# Wroom_board3motor.net
KiCad netlist of a schematic drawn in EAGLE
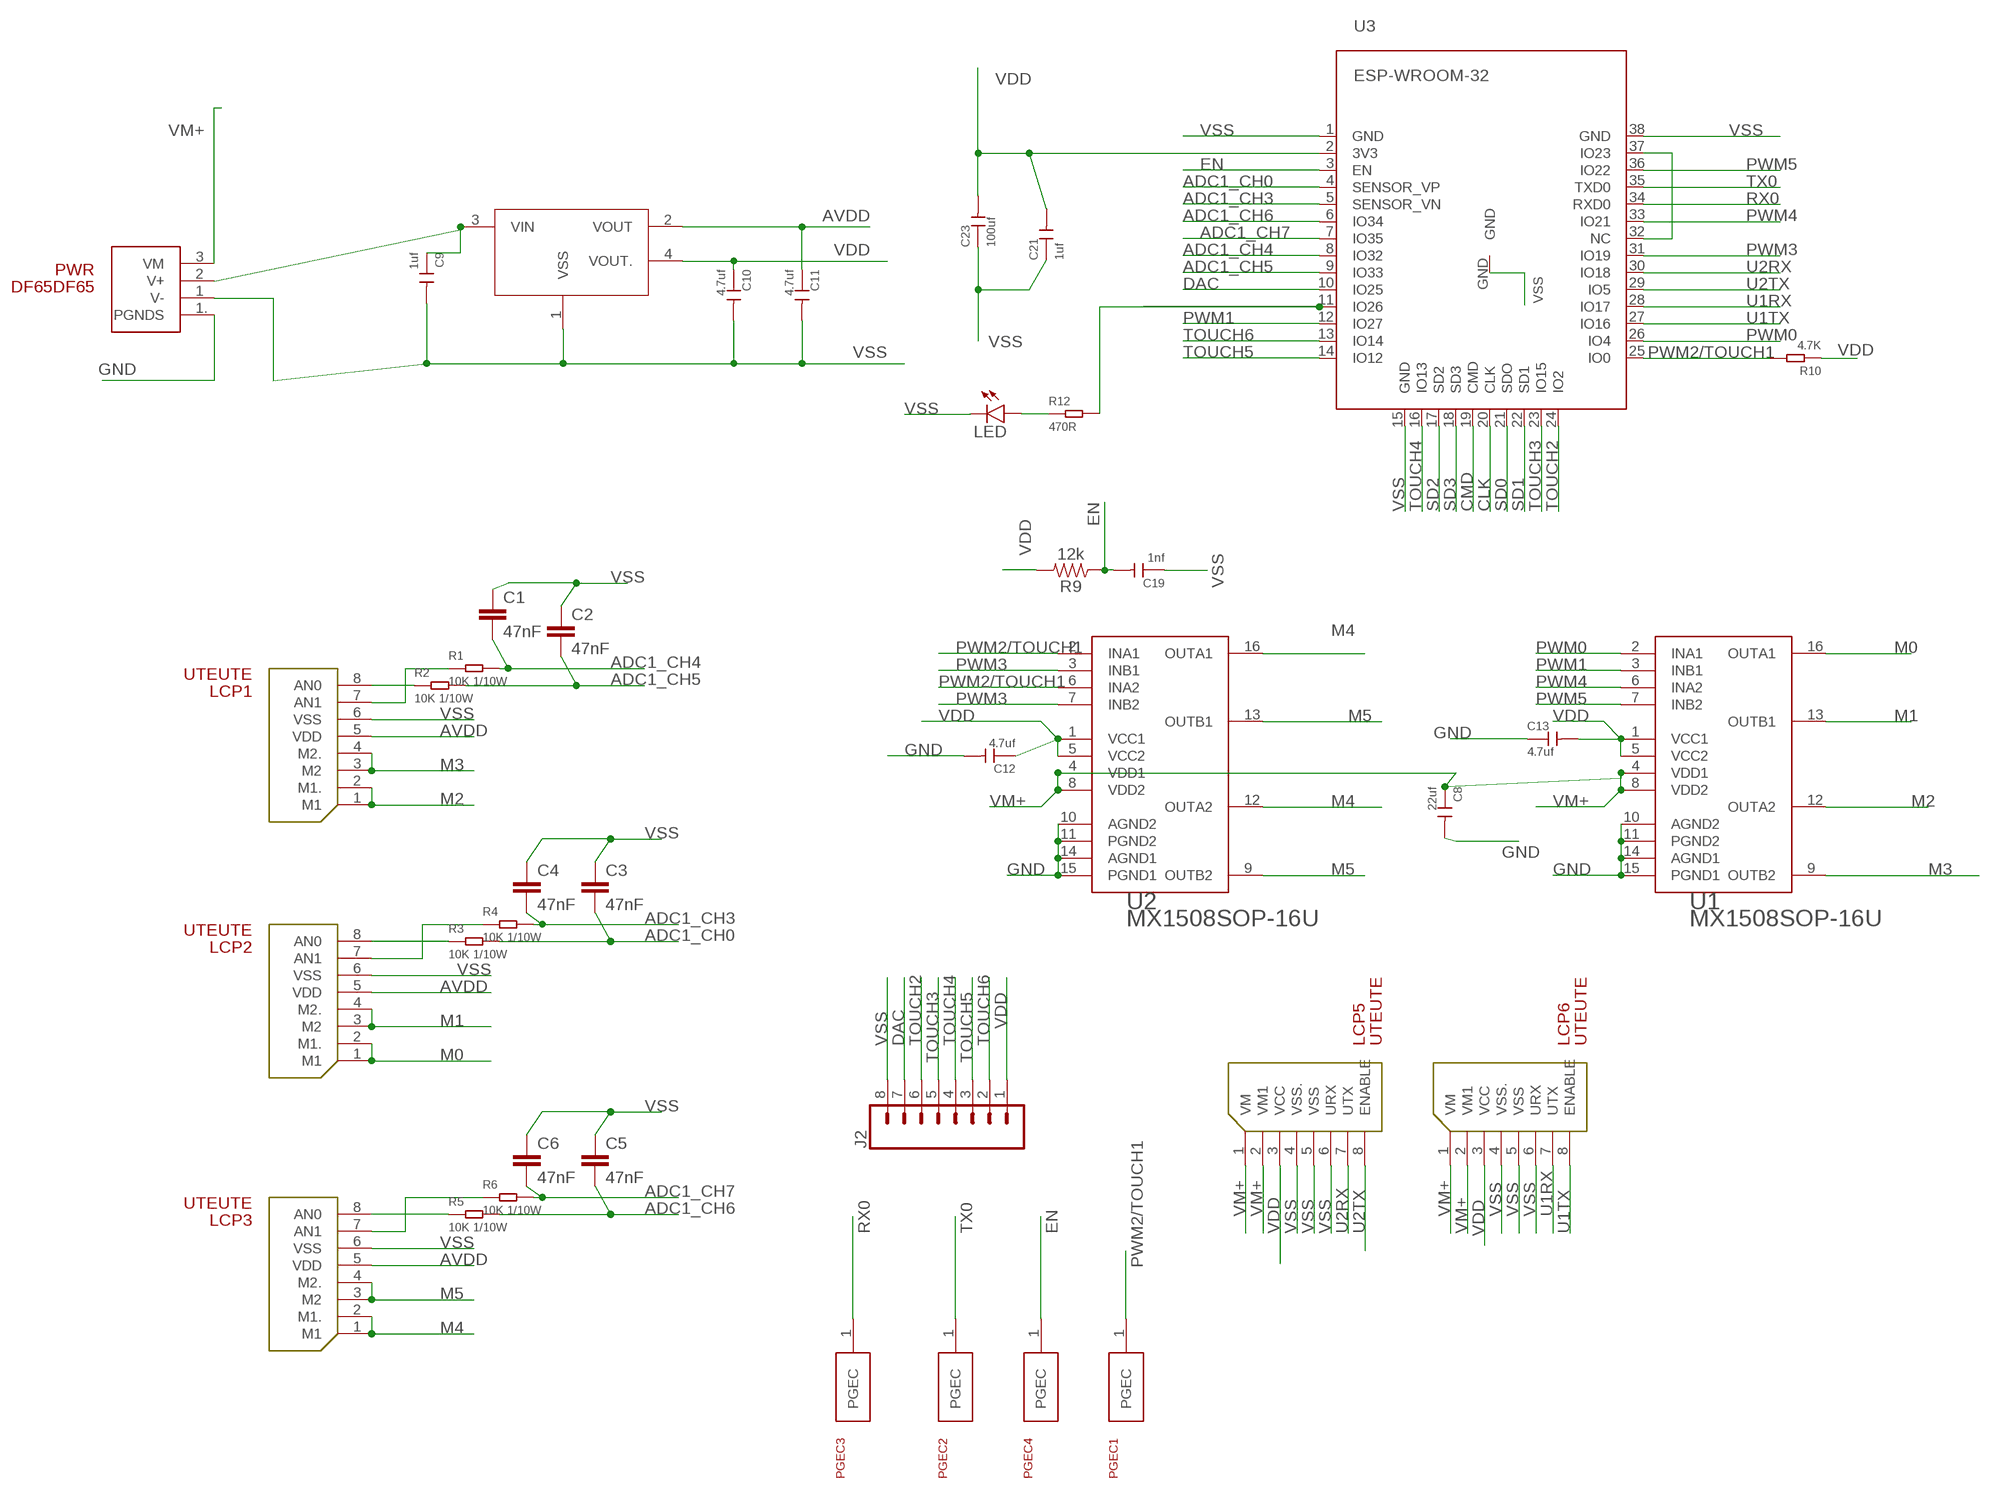
[diagram p0: schematic, sheet 1]

(export (version "E")
  (design (tool "Eeschema 10.0.6"))
  (components
    (comp (ref "C1")
      (value "47nF")
      (footprint "eagle-import:0603")
      (libsource (lib "eagle-import") (part "47NF-0603-25V-5%"))
    )
    (comp (ref "C2")
      (value "47nF")
      (footprint "eagle-import:0603")
      (libsource (lib "eagle-import") (part "47NF-0603-25V-5%"))
    )
    (comp (ref "C3")
      (value "47nF")
      (footprint "eagle-import:0603")
      (libsource (lib "eagle-import") (part "47NF-0603-25V-5%"))
    )
    (comp (ref "C4")
      (value "47nF")
      (footprint "eagle-import:0603")
      (libsource (lib "eagle-import") (part "47NF-0603-25V-5%"))
    )
    (comp (ref "C5")
      (value "47nF")
      (footprint "eagle-import:0603")
      (libsource (lib "eagle-import") (part "47NF-0603-25V-5%"))
    )
    (comp (ref "C6")
      (value "47nF")
      (footprint "eagle-import:0603")
      (libsource (lib "eagle-import") (part "47NF-0603-25V-5%"))
    )
    (comp (ref "C8")
      (value "22uf")
      (footprint "eagle-import:C0805")
      (fields (field (name "MPN") "CC0805MKX5R5BB226"))
      (libsource (lib "eagle-import") (part "CERAMIC-22UF-6.3V-20%-X5R(0805)"))
    )
    (comp (ref "C9")
      (value "1uf")
      (footprint "eagle-import:C0603")
      (fields (field (name "MPN") "CC0603KRX7R8BB105"))
      (libsource (lib "eagle-import") (part "CERAMIC-1UF-25V-10%-X7R(0603)"))
    )
    (comp (ref "C10")
      (value "4.7uf")
      (footprint "eagle-import:C0603")
      (fields (field (name "MPN") "CC0603KRX5R6BB475"))
      (libsource (lib "eagle-import") (part "CERAMIC-4.7UF-10V-10%-X5R(0603)"))
    )
    (comp (ref "C11")
      (value "4.7uf")
      (footprint "eagle-import:C0603")
      (fields (field (name "MPN") "CC0603KRX5R6BB475"))
      (libsource (lib "eagle-import") (part "CERAMIC-4.7UF-10V-10%-X5R(0603)"))
    )
    (comp (ref "C12")
      (value "4.7uf")
      (footprint "eagle-import:C0603")
      (fields (field (name "MPN") "CC0603KRX5R6BB475"))
      (libsource (lib "eagle-import") (part "CERAMIC-4.7UF-10V-10%-X5R(0603)"))
    )
    (comp (ref "C13")
      (value "4.7uf")
      (footprint "eagle-import:C0603")
      (fields (field (name "MPN") "CC0603KRX5R6BB475"))
      (libsource (lib "eagle-import") (part "CERAMIC-4.7UF-10V-10%-X5R(0603)"))
    )
    (comp (ref "C19")
      (value "1nf")
      (footprint "eagle-import:C0603")
      (fields (field (name "MPN") "GRM1885C1H102JA01D"))
      (libsource (lib "eagle-import") (part "CERAMIC-1NF-50V-5%-C0G(0603)"))
    )
    (comp (ref "C21")
      (value "1uf")
      (footprint "eagle-import:C0603")
      (fields (field (name "MPN") "CC0603KRX7R8BB105"))
      (libsource (lib "eagle-import") (part "CERAMIC-1UF-25V-10%-X7R(0603)"))
    )
    (comp (ref "C23")
      (value "100uf")
      (footprint "eagle-import:C1206")
      (fields (field (name "MPN") "GRM31CR60J107ME39L"))
      (libsource (lib "eagle-import") (part "CERAMIC-100UF-6.3V-20%-X5R(1206)"))
    )
    (comp (ref "J2")
      (value "CONN_08\"")
      (footprint "eagle-import:1X08")
      (libsource (lib "eagle-import") (part "CONN_08{dblquote}"))
    )
    (comp (ref "LCP1")
      (value "UTEUTE")
      (footprint "eagle-import:UTE")
      (libsource (lib "eagle-import") (part "UTEUTE"))
    )
    (comp (ref "LCP2")
      (value "UTEUTE")
      (footprint "eagle-import:UTE")
      (libsource (lib "eagle-import") (part "UTEUTE"))
    )
    (comp (ref "LCP3")
      (value "UTEUTE")
      (footprint "eagle-import:UTE")
      (libsource (lib "eagle-import") (part "UTEUTE"))
    )
    (comp (ref "LCP5")
      (value "UTEUTE")
      (footprint "eagle-import:UTE")
      (libsource (lib "eagle-import") (part "ute5526(uart)_UTEUTE"))
    )
    (comp (ref "LCP6")
      (value "UTEUTE")
      (footprint "eagle-import:UTE")
      (libsource (lib "eagle-import") (part "ute5526(uart)_UTEUTE"))
    )
    (comp (ref "LED")
      (value "LEDCHIP-LED0603")
      (footprint "eagle-import:CHIP-LED0603")
      (libsource (lib "eagle-import") (part "LEDCHIP-LED0603"))
    )
    (comp (ref "PGEC1")
      (value "PGECPGEC")
      (footprint "eagle-import:PGEC")
      (libsource (lib "eagle-import") (part "PGECPGEC"))
    )
    (comp (ref "PGEC2")
      (value "PGECPGEC")
      (footprint "eagle-import:PGEC")
      (libsource (lib "eagle-import") (part "PGECPGEC"))
    )
    (comp (ref "PGEC3")
      (value "PGECPGEC")
      (footprint "eagle-import:PGEC")
      (libsource (lib "eagle-import") (part "PGECPGEC"))
    )
    (comp (ref "PGEC4")
      (value "PGECPGEC")
      (footprint "eagle-import:PGEC")
      (libsource (lib "eagle-import") (part "PGECPGEC"))
    )
    (comp (ref "PWR")
      (value "DF65DF65")
      (footprint "eagle-import:DF65")
      (libsource (lib "eagle-import") (part "DF65DF65"))
    )
    (comp (ref "R1")
      (value "10K 1/10W")
      (footprint "eagle-import:R0603")
      (fields (field (name "MPN") "RC0603JR-0710KL"))
      (libsource (lib "eagle-import") (part "SMD-RES-10K-5%-1/10W(0603)"))
    )
    (comp (ref "R2")
      (value "10K 1/10W")
      (footprint "eagle-import:R0603")
      (fields (field (name "MPN") "RC0603JR-0710KL"))
      (libsource (lib "eagle-import") (part "SMD-RES-10K-5%-1/10W(0603)"))
    )
    (comp (ref "R3")
      (value "10K 1/10W")
      (footprint "eagle-import:R0603")
      (fields (field (name "MPN") "RC0603JR-0710KL"))
      (libsource (lib "eagle-import") (part "SMD-RES-10K-5%-1/10W(0603)"))
    )
    (comp (ref "R4")
      (value "10K 1/10W")
      (footprint "eagle-import:R0603")
      (fields (field (name "MPN") "RC0603JR-0710KL"))
      (libsource (lib "eagle-import") (part "SMD-RES-10K-5%-1/10W(0603)"))
    )
    (comp (ref "R5")
      (value "10K 1/10W")
      (footprint "eagle-import:R0603")
      (fields (field (name "MPN") "RC0603JR-0710KL"))
      (libsource (lib "eagle-import") (part "SMD-RES-10K-5%-1/10W(0603)"))
    )
    (comp (ref "R6")
      (value "10K 1/10W")
      (footprint "eagle-import:R0603")
      (fields (field (name "MPN") "RC0603JR-0710KL"))
      (libsource (lib "eagle-import") (part "SMD-RES-10K-5%-1/10W(0603)"))
    )
    (comp (ref "R9")
      (value "12k")
      (footprint "eagle-import:0603")
      (libsource (lib "eagle-import") (part "12KOHM-0603-1/10W-1%"))
    )
    (comp (ref "R10")
      (value "4.7K")
      (footprint "eagle-import:R0603")
      (fields (field (name "MPN") "RC0603JR-074K7L"))
      (libsource (lib "eagle-import") (part "SMD-RES-4.7K-5%-1/10W(0603)"))
    )
    (comp (ref "R12")
      (value "470R")
      (footprint "eagle-import:R0603")
      (fields (field (name "MPN") "RC0603JR-07470RL"))
      (libsource (lib "eagle-import") (part "SMD-RES-470R-5%-1/10W(0603)"))
    )
    (comp (ref "U1")
      (value "MX1508SOP-16U")
      (footprint "eagle-import:MX1508SOP-16")
      (libsource (lib "eagle-import") (part "MX1508SOP-16U"))
    )
    (comp (ref "U2")
      (value "MX1508SOP-16U")
      (footprint "eagle-import:MX1508SOP-16")
      (libsource (lib "eagle-import") (part "MX1508SOP-16U"))
    )
    (comp (ref "U3")
      (value "ESP-WROOM-32")
      (footprint "eagle-import:ESP-WROOM-32")
      (libsource (lib "eagle-import") (part "ESP-WROOM-32"))
    )
    (comp (ref "U4")
      (value "SOT230P700X180-4NLDL1117")
      (footprint "eagle-import:SOT230P700X180-4N")
      (libsource (lib "eagle-import") (part "SOT230P700X180-4NLDL1117"))
    )
  )
  (nets
    (net (code "1") (name "/ADC1_CH0") (class "Default")
      (node (ref "C3") (pin "2") (pinfunction "2_2") (pintype "passive"))
      (node (ref "R3") (pin "2") (pinfunction "2_2") (pintype "passive"))
      (node (ref "U3") (pin "4") (pinfunction "SENSOR_VP_4") (pintype "bidirectional"))
    )
    (net (code "2") (name "/ADC1_CH3") (class "Default")
      (node (ref "C4") (pin "2") (pinfunction "2_2") (pintype "passive"))
      (node (ref "R4") (pin "2") (pinfunction "2_2") (pintype "passive"))
      (node (ref "U3") (pin "5") (pinfunction "SENSOR_VN_5") (pintype "bidirectional"))
    )
    (net (code "3") (name "/ADC1_CH4") (class "Default")
      (node (ref "C1") (pin "2") (pinfunction "2_2") (pintype "passive"))
      (node (ref "R1") (pin "2") (pinfunction "2_2") (pintype "passive"))
      (node (ref "U3") (pin "8") (pinfunction "IO32_8") (pintype "bidirectional"))
    )
    (net (code "4") (name "/ADC1_CH5") (class "Default")
      (node (ref "C2") (pin "2") (pinfunction "2_2") (pintype "passive"))
      (node (ref "R2") (pin "2") (pinfunction "2_2") (pintype "passive"))
      (node (ref "U3") (pin "9") (pinfunction "IO33_9") (pintype "bidirectional"))
    )
    (net (code "5") (name "/ADC1_CH6") (class "Default")
      (node (ref "C5") (pin "2") (pinfunction "2_2") (pintype "passive"))
      (node (ref "R5") (pin "2") (pinfunction "2_2") (pintype "passive"))
      (node (ref "U3") (pin "6") (pinfunction "IO34_6") (pintype "bidirectional"))
    )
    (net (code "6") (name "/ADC1_CH7") (class "Default")
      (node (ref "C6") (pin "2") (pinfunction "2_2") (pintype "passive"))
      (node (ref "R6") (pin "2") (pinfunction "2_2") (pintype "passive"))
      (node (ref "U3") (pin "7") (pinfunction "IO35_7") (pintype "bidirectional"))
    )
    (net (code "7") (name "/AVDD") (class "Default")
      (node (ref "C11") (pin "1") (pinfunction "1_1") (pintype "passive"))
      (node (ref "LCP1") (pin "5") (pinfunction "VDD_5") (pintype "bidirectional"))
      (node (ref "LCP2") (pin "5") (pinfunction "VDD_5") (pintype "bidirectional"))
      (node (ref "LCP3") (pin "5") (pinfunction "VDD_5") (pintype "bidirectional"))
      (node (ref "U4") (pin "2") (pinfunction "VOUT_2") (pintype "bidirectional"))
    )
    (net (code "8") (name "/CLK") (class "Default")
      (node (ref "U3") (pin "20") (pinfunction "CLK_20") (pintype "bidirectional"))
    )
    (net (code "9") (name "/CMD") (class "Default")
      (node (ref "U3") (pin "19") (pinfunction "CMD_19") (pintype "bidirectional"))
    )
    (net (code "10") (name "/DAC") (class "Default")
      (node (ref "J2") (pin "7") (pinfunction "7_7") (pintype "passive"))
      (node (ref "U3") (pin "10") (pinfunction "IO25_10") (pintype "bidirectional"))
    )
    (net (code "11") (name "/EN") (class "Default")
      (node (ref "C19") (pin "2") (pinfunction "2_2") (pintype "passive"))
      (node (ref "PGEC4") (pin "1") (pinfunction "PGEC_1") (pintype "bidirectional"))
      (node (ref "R9") (pin "1") (pinfunction "1_1") (pintype "passive"))
      (node (ref "U3") (pin "3") (pinfunction "EN_3") (pintype "bidirectional"))
    )
    (net (code "12") (name "/GND") (class "Default")
      (node (ref "C12") (pin "2") (pinfunction "2_2") (pintype "passive"))
      (node (ref "C13") (pin "1") (pinfunction "1_1") (pintype "passive"))
      (node (ref "C8") (pin "2") (pinfunction "2_2") (pintype "passive"))
      (node (ref "PWR") (pin "1.") (pinfunction "PGNDS_1.") (pintype "bidirectional"))
      (node (ref "U1") (pin "10") (pinfunction "AGND2_10") (pintype "bidirectional"))
      (node (ref "U1") (pin "11") (pinfunction "PGND2_11") (pintype "bidirectional"))
      (node (ref "U1") (pin "14") (pinfunction "AGND1_14") (pintype "bidirectional"))
      (node (ref "U1") (pin "15") (pinfunction "PGND1_15") (pintype "bidirectional"))
      (node (ref "U2") (pin "10") (pinfunction "AGND2_10") (pintype "bidirectional"))
      (node (ref "U2") (pin "11") (pinfunction "PGND2_11") (pintype "bidirectional"))
      (node (ref "U2") (pin "14") (pinfunction "AGND1_14") (pintype "bidirectional"))
      (node (ref "U2") (pin "15") (pinfunction "PGND1_15") (pintype "bidirectional"))
    )
    (net (code "13") (name "/M0") (class "Default")
      (node (ref "LCP2") (pin "1") (pinfunction "M1_1") (pintype "bidirectional"))
      (node (ref "LCP2") (pin "2") (pinfunction "M1._2") (pintype "bidirectional"))
      (node (ref "U1") (pin "16") (pinfunction "OUTA1_16") (pintype "bidirectional"))
    )
    (net (code "14") (name "/M1") (class "Default")
      (node (ref "LCP2") (pin "3") (pinfunction "M2_3") (pintype "bidirectional"))
      (node (ref "LCP2") (pin "4") (pinfunction "M2._4") (pintype "bidirectional"))
      (node (ref "U1") (pin "13") (pinfunction "OUTB1_13") (pintype "bidirectional"))
    )
    (net (code "15") (name "/M2") (class "Default")
      (node (ref "LCP1") (pin "1") (pinfunction "M1_1") (pintype "bidirectional"))
      (node (ref "LCP1") (pin "2") (pinfunction "M1._2") (pintype "bidirectional"))
      (node (ref "U1") (pin "12") (pinfunction "OUTA2_12") (pintype "bidirectional"))
    )
    (net (code "16") (name "/M3") (class "Default")
      (node (ref "LCP1") (pin "3") (pinfunction "M2_3") (pintype "bidirectional"))
      (node (ref "LCP1") (pin "4") (pinfunction "M2._4") (pintype "bidirectional"))
      (node (ref "U1") (pin "9") (pinfunction "OUTB2_9") (pintype "bidirectional"))
    )
    (net (code "17") (name "/M4") (class "Default")
      (node (ref "LCP3") (pin "1") (pinfunction "M1_1") (pintype "bidirectional"))
      (node (ref "LCP3") (pin "2") (pinfunction "M1._2") (pintype "bidirectional"))
      (node (ref "U2") (pin "12") (pinfunction "OUTA2_12") (pintype "bidirectional"))
      (node (ref "U2") (pin "16") (pinfunction "OUTA1_16") (pintype "bidirectional"))
    )
    (net (code "18") (name "/M5") (class "Default")
      (node (ref "LCP3") (pin "3") (pinfunction "M2_3") (pintype "bidirectional"))
      (node (ref "LCP3") (pin "4") (pinfunction "M2._4") (pintype "bidirectional"))
      (node (ref "U2") (pin "13") (pinfunction "OUTB1_13") (pintype "bidirectional"))
      (node (ref "U2") (pin "9") (pinfunction "OUTB2_9") (pintype "bidirectional"))
    )
    (net (code "19") (name "/PWM0") (class "Default")
      (node (ref "U1") (pin "2") (pinfunction "INA1_2") (pintype "bidirectional"))
      (node (ref "U3") (pin "26") (pinfunction "IO4_26") (pintype "bidirectional"))
    )
    (net (code "20") (name "/PWM1") (class "Default")
      (node (ref "U1") (pin "3") (pinfunction "INB1_3") (pintype "bidirectional"))
      (node (ref "U3") (pin "12") (pinfunction "IO27_12") (pintype "bidirectional"))
    )
    (net (code "21") (name "/PWM2{slash}TOUCH1") (class "Default")
      (node (ref "PGEC1") (pin "1") (pinfunction "PGEC_1") (pintype "bidirectional"))
      (node (ref "R10") (pin "2") (pinfunction "2_2") (pintype "passive"))
      (node (ref "U2") (pin "2") (pinfunction "INA1_2") (pintype "bidirectional"))
      (node (ref "U2") (pin "6") (pinfunction "INA2_6") (pintype "bidirectional"))
      (node (ref "U3") (pin "25") (pinfunction "IO0_25") (pintype "bidirectional"))
    )
    (net (code "22") (name "/PWM3") (class "Default")
      (node (ref "U2") (pin "3") (pinfunction "INB1_3") (pintype "bidirectional"))
      (node (ref "U2") (pin "7") (pinfunction "INB2_7") (pintype "bidirectional"))
      (node (ref "U3") (pin "31") (pinfunction "IO19_31") (pintype "bidirectional"))
    )
    (net (code "23") (name "/PWM4") (class "Default")
      (node (ref "U1") (pin "6") (pinfunction "INA2_6") (pintype "bidirectional"))
      (node (ref "U3") (pin "33") (pinfunction "IO21_33") (pintype "bidirectional"))
    )
    (net (code "24") (name "/PWM5") (class "Default")
      (node (ref "U1") (pin "7") (pinfunction "INB2_7") (pintype "bidirectional"))
      (node (ref "U3") (pin "36") (pinfunction "IO22_36") (pintype "bidirectional"))
    )
    (net (code "25") (name "/RX0") (class "Default")
      (node (ref "PGEC3") (pin "1") (pinfunction "PGEC_1") (pintype "bidirectional"))
      (node (ref "U3") (pin "34") (pinfunction "RXD0_34") (pintype "bidirectional"))
    )
    (net (code "26") (name "/SD0") (class "Default")
      (node (ref "U3") (pin "21") (pinfunction "SDO_21") (pintype "bidirectional"))
    )
    (net (code "27") (name "/SD1") (class "Default")
      (node (ref "U3") (pin "22") (pinfunction "SD1_22") (pintype "bidirectional"))
    )
    (net (code "28") (name "/SD2") (class "Default")
      (node (ref "U3") (pin "17") (pinfunction "SD2_17") (pintype "bidirectional"))
    )
    (net (code "29") (name "/SD3") (class "Default")
      (node (ref "U3") (pin "18") (pinfunction "SD3_18") (pintype "bidirectional"))
    )
    (net (code "30") (name "/TOUCH2") (class "Default")
      (node (ref "J2") (pin "6") (pinfunction "6_6") (pintype "passive"))
      (node (ref "U3") (pin "24") (pinfunction "IO2_24") (pintype "bidirectional"))
    )
    (net (code "31") (name "/TOUCH3") (class "Default")
      (node (ref "J2") (pin "5") (pinfunction "5_5") (pintype "passive"))
      (node (ref "U3") (pin "23") (pinfunction "IO15_23") (pintype "bidirectional"))
    )
    (net (code "32") (name "/TOUCH4") (class "Default")
      (node (ref "J2") (pin "4") (pinfunction "4_4") (pintype "passive"))
      (node (ref "U3") (pin "16") (pinfunction "IO13_16") (pintype "bidirectional"))
    )
    (net (code "33") (name "/TOUCH5") (class "Default")
      (node (ref "J2") (pin "3") (pinfunction "3_3") (pintype "passive"))
      (node (ref "U3") (pin "14") (pinfunction "IO12_14") (pintype "bidirectional"))
    )
    (net (code "34") (name "/TOUCH6") (class "Default")
      (node (ref "J2") (pin "2") (pinfunction "2_2") (pintype "passive"))
      (node (ref "U3") (pin "13") (pinfunction "IO14_13") (pintype "bidirectional"))
    )
    (net (code "35") (name "/TX0") (class "Default")
      (node (ref "PGEC2") (pin "1") (pinfunction "PGEC_1") (pintype "bidirectional"))
      (node (ref "U3") (pin "35") (pinfunction "TXD0_35") (pintype "bidirectional"))
    )
    (net (code "36") (name "/U1RX") (class "Default")
      (node (ref "LCP6") (pin "7") (pinfunction "UTX_7") (pintype "bidirectional"))
      (node (ref "U3") (pin "28") (pinfunction "IO17_28") (pintype "bidirectional"))
    )
    (net (code "37") (name "/U1TX") (class "Default")
      (node (ref "LCP6") (pin "8") (pinfunction "ENABLE_8") (pintype "bidirectional"))
      (node (ref "U3") (pin "27") (pinfunction "IO16_27") (pintype "bidirectional"))
    )
    (net (code "38") (name "/U2RX") (class "Default")
      (node (ref "LCP5") (pin "7") (pinfunction "UTX_7") (pintype "bidirectional"))
      (node (ref "U3") (pin "30") (pinfunction "IO18_30") (pintype "bidirectional"))
    )
    (net (code "39") (name "/U2TX") (class "Default")
      (node (ref "LCP5") (pin "8") (pinfunction "ENABLE_8") (pintype "bidirectional"))
      (node (ref "U3") (pin "29") (pinfunction "IO5_29") (pintype "bidirectional"))
    )
    (net (code "40") (name "/VDD") (class "Default")
      (node (ref "C10") (pin "1") (pinfunction "1_1") (pintype "passive"))
      (node (ref "C12") (pin "1") (pinfunction "1_1") (pintype "passive"))
      (node (ref "C13") (pin "2") (pinfunction "2_2") (pintype "passive"))
      (node (ref "C21") (pin "2") (pinfunction "2_2") (pintype "passive"))
      (node (ref "C23") (pin "2") (pinfunction "2_2") (pintype "passive"))
      (node (ref "J2") (pin "1") (pinfunction "1_1") (pintype "passive"))
      (node (ref "LCP5") (pin "3") (pinfunction "VCC_3") (pintype "bidirectional"))
      (node (ref "LCP6") (pin "3") (pinfunction "VCC_3") (pintype "bidirectional"))
      (node (ref "R10") (pin "1") (pinfunction "1_1") (pintype "passive"))
      (node (ref "R9") (pin "2") (pinfunction "2_2") (pintype "passive"))
      (node (ref "U1") (pin "1") (pinfunction "VCC1_1") (pintype "bidirectional"))
      (node (ref "U1") (pin "5") (pinfunction "VCC2_5") (pintype "bidirectional"))
      (node (ref "U2") (pin "1") (pinfunction "VCC1_1") (pintype "bidirectional"))
      (node (ref "U2") (pin "5") (pinfunction "VCC2_5") (pintype "bidirectional"))
      (node (ref "U3") (pin "2") (pinfunction "3V3_2") (pintype "bidirectional"))
      (node (ref "U4") (pin "4") (pinfunction "VOUT._4") (pintype "bidirectional"))
    )
    (net (code "41") (name "/VM+") (class "Default")
      (node (ref "C8") (pin "1") (pinfunction "1_1") (pintype "passive"))
      (node (ref "LCP5") (pin "1") (pinfunction "VM_1") (pintype "bidirectional"))
      (node (ref "LCP5") (pin "2") (pinfunction "VM1_2") (pintype "bidirectional"))
      (node (ref "LCP6") (pin "1") (pinfunction "VM_1") (pintype "bidirectional"))
      (node (ref "LCP6") (pin "2") (pinfunction "VM1_2") (pintype "bidirectional"))
      (node (ref "PWR") (pin "3") (pinfunction "VM_3") (pintype "bidirectional"))
      (node (ref "U1") (pin "4") (pinfunction "VDD1_4") (pintype "bidirectional"))
      (node (ref "U1") (pin "8") (pinfunction "VDD2_8") (pintype "bidirectional"))
      (node (ref "U2") (pin "4") (pinfunction "VDD1_4") (pintype "bidirectional"))
      (node (ref "U2") (pin "8") (pinfunction "VDD2_8") (pintype "bidirectional"))
    )
    (net (code "42") (name "/VSS") (class "Default")
      (node (ref "C1") (pin "1") (pinfunction "1_1") (pintype "passive"))
      (node (ref "C10") (pin "2") (pinfunction "2_2") (pintype "passive"))
      (node (ref "C11") (pin "2") (pinfunction "2_2") (pintype "passive"))
      (node (ref "C19") (pin "1") (pinfunction "1_1") (pintype "passive"))
      (node (ref "C2") (pin "1") (pinfunction "1_1") (pintype "passive"))
      (node (ref "C21") (pin "1") (pinfunction "1_1") (pintype "passive"))
      (node (ref "C23") (pin "1") (pinfunction "1_1") (pintype "passive"))
      (node (ref "C3") (pin "1") (pinfunction "1_1") (pintype "passive"))
      (node (ref "C4") (pin "1") (pinfunction "1_1") (pintype "passive"))
      (node (ref "C5") (pin "1") (pinfunction "1_1") (pintype "passive"))
      (node (ref "C6") (pin "1") (pinfunction "1_1") (pintype "passive"))
      (node (ref "C9") (pin "2") (pinfunction "2_2") (pintype "passive"))
      (node (ref "J2") (pin "8") (pinfunction "8_8") (pintype "passive"))
      (node (ref "LCP1") (pin "6") (pinfunction "VSS_6") (pintype "bidirectional"))
      (node (ref "LCP2") (pin "6") (pinfunction "VSS_6") (pintype "bidirectional"))
      (node (ref "LCP3") (pin "6") (pinfunction "VSS_6") (pintype "bidirectional"))
      (node (ref "LCP5") (pin "4") (pinfunction "VSS._4") (pintype "bidirectional"))
      (node (ref "LCP5") (pin "5") (pinfunction "VSS_5") (pintype "bidirectional"))
      (node (ref "LCP5") (pin "6") (pinfunction "URX_6") (pintype "bidirectional"))
      (node (ref "LCP6") (pin "4") (pinfunction "VSS._4") (pintype "bidirectional"))
      (node (ref "LCP6") (pin "5") (pinfunction "VSS_5") (pintype "bidirectional"))
      (node (ref "LCP6") (pin "6") (pinfunction "URX_6") (pintype "bidirectional"))
      (node (ref "LED") (pin "C") (pinfunction "C_C") (pintype "passive"))
      (node (ref "PWR") (pin "1") (pinfunction "V-_1") (pintype "bidirectional"))
      (node (ref "U3") (pin "1") (pinfunction "GND_1") (pintype "bidirectional"))
      (node (ref "U3") (pin "15") (pinfunction "GND_15") (pintype "bidirectional"))
      (node (ref "U3") (pin "38") (pinfunction "GND_38") (pintype "bidirectional"))
      (node (ref "U3") (pin "GND") (pinfunction "GND_GND") (pintype "bidirectional"))
      (node (ref "U4") (pin "1") (pinfunction "VSS_1") (pintype "bidirectional"))
    )
    (net (code "43") (name "Net-(LCP1-AN0)") (class "Default")
      (node (ref "LCP1") (pin "8") (pinfunction "AN0_8") (pintype "bidirectional"))
      (node (ref "R2") (pin "1") (pinfunction "1_1") (pintype "passive"))
    )
    (net (code "44") (name "Net-(LCP1-AN1)") (class "Default")
      (node (ref "LCP1") (pin "7") (pinfunction "AN1_7") (pintype "bidirectional"))
      (node (ref "R1") (pin "1") (pinfunction "1_1") (pintype "passive"))
    )
    (net (code "45") (name "Net-(LCP2-AN0)") (class "Default")
      (node (ref "LCP2") (pin "8") (pinfunction "AN0_8") (pintype "bidirectional"))
      (node (ref "R3") (pin "1") (pinfunction "1_1") (pintype "passive"))
    )
    (net (code "46") (name "Net-(LCP2-AN1)") (class "Default")
      (node (ref "LCP2") (pin "7") (pinfunction "AN1_7") (pintype "bidirectional"))
      (node (ref "R4") (pin "1") (pinfunction "1_1") (pintype "passive"))
    )
    (net (code "47") (name "Net-(LCP3-AN0)") (class "Default")
      (node (ref "LCP3") (pin "8") (pinfunction "AN0_8") (pintype "bidirectional"))
      (node (ref "R5") (pin "1") (pinfunction "1_1") (pintype "passive"))
    )
    (net (code "48") (name "Net-(LCP3-AN1)") (class "Default")
      (node (ref "LCP3") (pin "7") (pinfunction "AN1_7") (pintype "bidirectional"))
      (node (ref "R6") (pin "1") (pinfunction "1_1") (pintype "passive"))
    )
    (net (code "49") (name "Net-(LED-PadA)") (class "Default")
      (node (ref "LED") (pin "A") (pinfunction "A_A") (pintype "passive"))
      (node (ref "R12") (pin "1") (pinfunction "1_1") (pintype "passive"))
    )
    (net (code "50") (name "Net-(PWR-V+)") (class "Default")
      (node (ref "C9") (pin "1") (pinfunction "1_1") (pintype "passive"))
      (node (ref "PWR") (pin "2") (pinfunction "V+_2") (pintype "bidirectional"))
      (node (ref "U4") (pin "3") (pinfunction "VIN_3") (pintype "bidirectional"))
    )
    (net (code "51") (name "Net-(U3-IO23)") (class "Default")
      (node (ref "U3") (pin "32") (pinfunction "NC_32") (pintype "bidirectional"))
      (node (ref "U3") (pin "37") (pinfunction "IO23_37") (pintype "bidirectional"))
    )
    (net (code "52") (name "Net-(U3-IO26)") (class "Default")
      (node (ref "R12") (pin "2") (pinfunction "2_2") (pintype "passive"))
      (node (ref "U3") (pin "11") (pinfunction "IO26_11") (pintype "bidirectional"))
    )
  )
)
